# HeartBeatAuditoryFeedbackV1.net
KiCad netlist of a schematic drawn in EAGLE
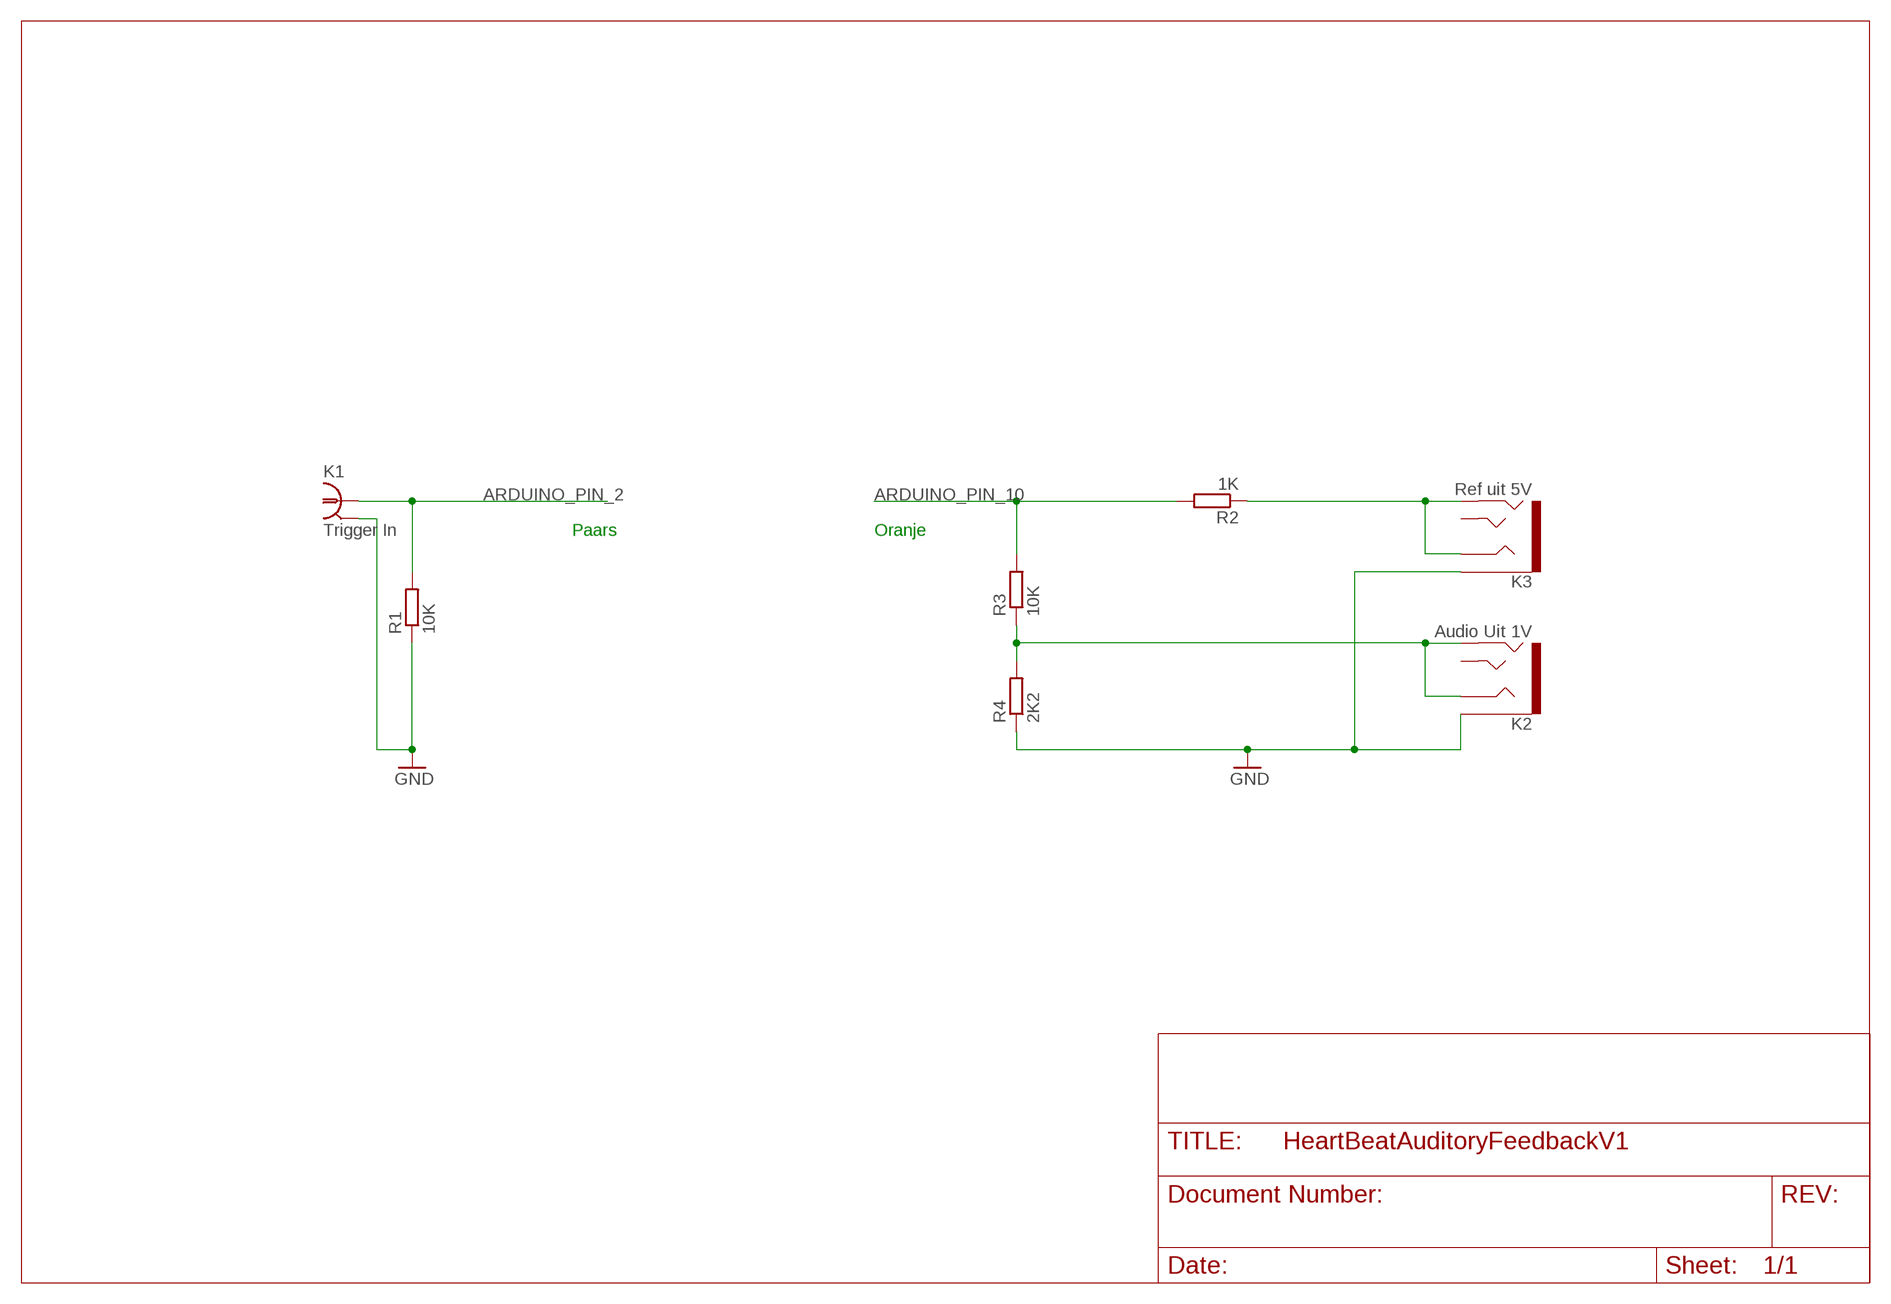
[diagram p0: schematic, sheet 1]

(export (version "E")
  (design (tool "Eeschema 10.0.6"))
  (components
    (comp (ref "K1")
      (value "Trigger In")
      (footprint "eagle-import:B35N61")
      (libsource (lib "eagle-import") (part "BN35N61"))
    )
    (comp (ref "K2")
      (value "Audio Uit 1V")
      (footprint "eagle-import:AUDIO_JACK_3.5MM_TRRS_SMD_RA")
      (libsource (lib "eagle-import") (part "AUDIO_JACK_TRRSSMD_RA"))
    )
    (comp (ref "K3")
      (value "Ref uit 5V")
      (footprint "eagle-import:AUDIO_JACK_3.5MM_TRRS_SMD_RA")
      (libsource (lib "eagle-import") (part "AUDIO_JACK_TRRSSMD_RA"))
    )
    (comp (ref "R1")
      (value "10K")
      (footprint "eagle-import:0204_7")
      (libsource (lib "eagle-import") (part "R-EU_0204/7"))
    )
    (comp (ref "R2")
      (value "1K")
      (footprint "eagle-import:0204_7")
      (libsource (lib "eagle-import") (part "R-EU_0204/7"))
    )
    (comp (ref "R3")
      (value "10K")
      (footprint "eagle-import:0204_7")
      (libsource (lib "eagle-import") (part "R-EU_0204/7"))
    )
    (comp (ref "R4")
      (value "2K2")
      (footprint "eagle-import:0204_7")
      (libsource (lib "eagle-import") (part "R-EU_0204/7"))
    )
  )
  (nets
    (net (code "1") (name "/ARDUINO_PIN_2") (class "Default")
      (node (ref "K1") (pin "1") (pinfunction "1_1") (pintype "passive"))
      (node (ref "R1") (pin "2") (pinfunction "2_2") (pintype "passive"))
    )
    (net (code "2") (name "/ARDUINO_PIN_10") (class "Default")
      (node (ref "R2") (pin "2") (pinfunction "2_2") (pintype "passive"))
      (node (ref "R3") (pin "2") (pinfunction "2_2") (pintype "passive"))
    )
    (net (code "3") (name "GND") (class "Default")
      (node (ref "K1") (pin "2") (pinfunction "2_2") (pintype "passive"))
      (node (ref "K1") (pin "3") (pinfunction "2_3") (pintype "passive"))
      (node (ref "K1") (pin "4") (pinfunction "2_4") (pintype "passive"))
      (node (ref "K1") (pin "5") (pinfunction "2_5") (pintype "passive"))
      (node (ref "K2") (pin "EARTH") (pinfunction "EARTH_EARTH") (pintype "bidirectional"))
      (node (ref "K3") (pin "EARTH") (pinfunction "EARTH_EARTH") (pintype "bidirectional"))
      (node (ref "R1") (pin "1") (pinfunction "1_1") (pintype "passive"))
      (node (ref "R4") (pin "1") (pinfunction "1_1") (pintype "passive"))
    )
    (net (code "4") (name "Net-(K2-PadRING1)") (class "Default")
      (node (ref "K2") (pin "RING1") (pinfunction "RING1_RING1") (pintype "bidirectional"))
      (node (ref "K2") (pin "RING2") (pinfunction "RING2_RING2") (pintype "bidirectional"))
      (node (ref "R3") (pin "1") (pinfunction "1_1") (pintype "passive"))
      (node (ref "R4") (pin "2") (pinfunction "2_2") (pintype "passive"))
    )
    (net (code "5") (name "Net-(K3-PadRING1)") (class "Default")
      (node (ref "K3") (pin "RING1") (pinfunction "RING1_RING1") (pintype "bidirectional"))
      (node (ref "K3") (pin "RING2") (pinfunction "RING2_RING2") (pintype "bidirectional"))
      (node (ref "R2") (pin "1") (pinfunction "1_1") (pintype "passive"))
    )
    (net (code "6") (name "unconnected-(K2-PadTIP)") (class "Default")
      (node (ref "K2") (pin "TIP") (pinfunction "TIP_TIP") (pintype "bidirectional"))
    )
    (net (code "7") (name "unconnected-(K3-PadTIP)") (class "Default")
      (node (ref "K3") (pin "TIP") (pinfunction "TIP_TIP") (pintype "bidirectional"))
    )
  )
)
